# ESP8266Watch-v1-Sch.net
KiCad netlist of a schematic drawn in Altium Designer
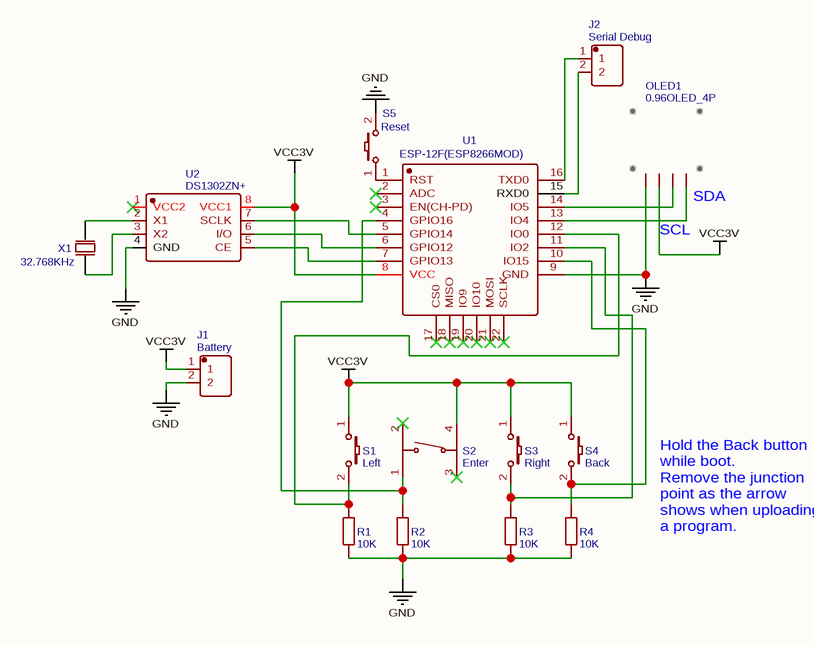
[diagram p0: ESP8266Watch-v1-Sch.schdoc]

(export (version "E")
  (design (tool "Eeschema 10.0.6"))
  (components
    (comp (ref "J1")
      (value "Battery")
      (fields (field (name "BOM_SUPPLIER PART") "C2324") (field (name "BOM_MANUFACTURER PART") "1.25T-1-2A"))
      (libsource (lib "altium-import") (part "root_0_Battery_"))
    )
    (comp (ref "J2")
      (value "Serial Debug")
      (fields (field (name "BOM_SUPPLIER PART") "C2324") (field (name "BOM_MANUFACTURER PART") "1.25T-1-2A"))
      (libsource (lib "altium-import") (part "root_0_Serial Debug_"))
    )
    (comp (ref "OLED1")
      (value "0.96OLED_4P")
      (fields (field (name "CONTRIBUTOR") "LCEDA_Lib"))
      (libsource (lib "altium-import") (part "root_0_0.96OLED_4P_"))
    )
    (comp (ref "R1")
      (value "10K")
      (fields
        (field (name "BOM_MANUFACTURER PART") "RT0603DRD0710KL")
        (field (name "BOM_SUPPLIER PART") "C136944")
        (field (name "CONTRIBUTOR") "LCSC")
      )
      (libsource (lib "altium-import") (part "root_1_10K_"))
    )
    (comp (ref "R2")
      (value "10K")
      (fields
        (field (name "BOM_MANUFACTURER PART") "RT0603DRD0710KL")
        (field (name "BOM_SUPPLIER PART") "C136944")
        (field (name "CONTRIBUTOR") "LCSC")
      )
      (libsource (lib "altium-import") (part "root_1_10K_"))
    )
    (comp (ref "R3")
      (value "10K")
      (fields
        (field (name "BOM_MANUFACTURER PART") "RT0603DRD0710KL")
        (field (name "BOM_SUPPLIER PART") "C136944")
        (field (name "CONTRIBUTOR") "LCSC")
      )
      (libsource (lib "altium-import") (part "root_1_10K_"))
    )
    (comp (ref "R4")
      (value "10K")
      (fields
        (field (name "BOM_MANUFACTURER PART") "RT0603DRD0710KL")
        (field (name "BOM_SUPPLIER PART") "C136944")
        (field (name "CONTRIBUTOR") "LCSC")
      )
      (libsource (lib "altium-import") (part "root_1_10K_"))
    )
    (comp (ref "S1")
      (value "Left")
      (fields
        (field (name "BOM_SUPPLIER PART") "C118141")
        (field (name "BOM_MANUFACTURER PART") "K2-1107ST-A4SW-06")
        (field (name "CONTRIBUTOR") "LCEDA_Lib")
      )
      (libsource (lib "altium-import") (part "root_3_Left_"))
    )
    (comp (ref "S2")
      (value "Enter")
      (fields
        (field (name "BOM_SUPPLIER PART") "C480319")
        (field (name "BOM_MANUFACTURER PART") "TS-1109S-B-F")
        (field (name "CONTRIBUTOR") "LCSC")
      )
      (libsource (lib "altium-import") (part "root_1_Enter_"))
    )
    (comp (ref "S3")
      (value "Right")
      (fields
        (field (name "BOM_SUPPLIER PART") "C118141")
        (field (name "BOM_MANUFACTURER PART") "K2-1107ST-A4SW-06")
        (field (name "CONTRIBUTOR") "LCEDA_Lib")
      )
      (libsource (lib "altium-import") (part "root_3_Right_"))
    )
    (comp (ref "S4")
      (value "Back")
      (fields
        (field (name "BOM_SUPPLIER PART") "C118141")
        (field (name "BOM_MANUFACTURER PART") "K2-1107ST-A4SW-06")
        (field (name "CONTRIBUTOR") "LCEDA_Lib")
      )
      (libsource (lib "altium-import") (part "root_3_Back_"))
    )
    (comp (ref "S5")
      (value "Reset")
      (fields
        (field (name "BOM_SUPPLIER PART") "C118141")
        (field (name "BOM_MANUFACTURER PART") "K2-1107ST-A4SW-06")
        (field (name "CONTRIBUTOR") "LCEDA_Lib")
      )
      (libsource (lib "altium-import") (part "root_1_Reset_"))
    )
    (comp (ref "U1")
      (value "ESP-12F(ESP8266MOD)")
      (fields (field (name "BOM_SUPPLIER PART") "C82891"))
      (libsource (lib "altium-import") (part "root_0_ESP-12F(ESP8266MOD)_"))
    )
    (comp (ref "U2")
      (value "DS1302ZN+")
      (fields (field (name "BOM_MANUFACTURER PART") "DS1302Z+T&R") (field (name "BOM_SUPPLIER PART") "C8959"))
      (libsource (lib "altium-import") (part "root_0_DS1302ZN+_"))
    )
    (comp (ref "X1")
      (value "32.768KHz")
      (fields
        (field (name "BOM_SUPPLIER PART") "C100098")
        (field (name "BOM_MANUFACTURER PART") "CFS-20632768DZFB")
        (field (name "CONTRIBUTOR") "LCSC")
      )
      (libsource (lib "altium-import") (part "root_1_32.768KHz_"))
    )
  )
  (nets
    (net (code "1") (name "GND") (class "Default")
      (node (ref "J1") (pin "2") (pinfunction "2_2") (pintype "passive"))
      (node (ref "OLED1") (pin "1") (pinfunction "1_1") (pintype "passive"))
      (node (ref "R1") (pin "1") (pinfunction "1_1") (pintype "passive"))
      (node (ref "R2") (pin "1") (pinfunction "1_1") (pintype "passive"))
      (node (ref "R3") (pin "1") (pinfunction "1_1") (pintype "passive"))
      (node (ref "R4") (pin "1") (pinfunction "1_1") (pintype "passive"))
      (node (ref "S5") (pin "2") (pinfunction "2_2") (pintype "passive"))
      (node (ref "U1") (pin "9") (pinfunction "GND_9") (pintype "passive"))
      (node (ref "U2") (pin "4") (pinfunction "GND_4") (pintype "passive"))
    )
    (net (code "2") (name "Net-(U1-GPIO12)") (class "Default")
      (node (ref "U1") (pin "6") (pinfunction "GPIO12_6") (pintype "passive"))
      (node (ref "U2") (pin "6") (pinfunction "I/O_6") (pintype "passive"))
    )
    (net (code "3") (name "Net-(U1-GPIO13)") (class "Default")
      (node (ref "U1") (pin "7") (pinfunction "GPIO13_7") (pintype "passive"))
      (node (ref "U2") (pin "5") (pinfunction "CE_5") (pintype "passive"))
    )
    (net (code "4") (name "Net-(U1-GPIO14)") (class "Default")
      (node (ref "U1") (pin "5") (pinfunction "GPIO14_5") (pintype "passive"))
      (node (ref "U2") (pin "7") (pinfunction "SCLK_7") (pintype "passive"))
    )
    (net (code "5") (name "Net-(U1-GPIO16)") (class "Default")
      (node (ref "R2") (pin "2") (pinfunction "2_2") (pintype "passive"))
      (node (ref "S2") (pin "1") (pinfunction "1_1") (pintype "passive"))
      (node (ref "U1") (pin "4") (pinfunction "GPIO16_4") (pintype "passive"))
    )
    (net (code "6") (name "Net-(U1-IO0)") (class "Default")
      (node (ref "R1") (pin "2") (pinfunction "2_2") (pintype "passive"))
      (node (ref "S1") (pin "2") (pinfunction "2_2") (pintype "passive"))
      (node (ref "U1") (pin "12") (pinfunction "IO0_12") (pintype "passive"))
    )
    (net (code "7") (name "Net-(U1-IO2)") (class "Default")
      (node (ref "R3") (pin "2") (pinfunction "2_2") (pintype "passive"))
      (node (ref "S3") (pin "2") (pinfunction "2_2") (pintype "passive"))
      (node (ref "U1") (pin "11") (pinfunction "IO2_11") (pintype "passive"))
    )
    (net (code "8") (name "Net-(U1-IO4)") (class "Default")
      (node (ref "OLED1") (pin "4") (pinfunction "4_4") (pintype "passive"))
      (node (ref "U1") (pin "13") (pinfunction "IO4_13") (pintype "passive"))
    )
    (net (code "9") (name "Net-(U1-IO5)") (class "Default")
      (node (ref "OLED1") (pin "3") (pinfunction "3_3") (pintype "passive"))
      (node (ref "U1") (pin "14") (pinfunction "IO5_14") (pintype "passive"))
    )
    (net (code "10") (name "Net-(U1-IO15)") (class "Default")
      (node (ref "R4") (pin "2") (pinfunction "2_2") (pintype "passive"))
      (node (ref "S4") (pin "2") (pinfunction "2_2") (pintype "passive"))
      (node (ref "U1") (pin "10") (pinfunction "IO15_10") (pintype "passive"))
    )
    (net (code "11") (name "Net-(U1-RST)") (class "Default")
      (node (ref "S5") (pin "1") (pinfunction "1_1") (pintype "passive"))
      (node (ref "U1") (pin "1") (pinfunction "RST_1") (pintype "passive"))
    )
    (net (code "12") (name "Net-(U1-RXD0)") (class "Default")
      (node (ref "J2") (pin "2") (pinfunction "2_2") (pintype "passive"))
      (node (ref "U1") (pin "15") (pinfunction "RXD0_15") (pintype "passive"))
    )
    (net (code "13") (name "Net-(U1-TXD0)") (class "Default")
      (node (ref "J2") (pin "1") (pinfunction "1_1") (pintype "passive"))
      (node (ref "U1") (pin "16") (pinfunction "TXD0_16") (pintype "passive"))
    )
    (net (code "14") (name "Net-(U2-X1)") (class "Default")
      (node (ref "U2") (pin "2") (pinfunction "X1_2") (pintype "passive"))
      (node (ref "X1") (pin "2") (pinfunction "OSC2_2") (pintype "passive"))
    )
    (net (code "15") (name "Net-(U2-X2)") (class "Default")
      (node (ref "U2") (pin "3") (pinfunction "X2_3") (pintype "passive"))
      (node (ref "X1") (pin "1") (pinfunction "OSC1_1") (pintype "passive"))
    )
    (net (code "16") (name "VCC3V") (class "Default")
      (node (ref "J1") (pin "1") (pinfunction "1_1") (pintype "passive"))
      (node (ref "OLED1") (pin "2") (pinfunction "2_2") (pintype "passive"))
      (node (ref "S1") (pin "1") (pinfunction "1_1") (pintype "passive"))
      (node (ref "S2") (pin "4") (pinfunction "4_4") (pintype "passive"))
      (node (ref "S3") (pin "1") (pinfunction "1_1") (pintype "passive"))
      (node (ref "S4") (pin "1") (pinfunction "1_1") (pintype "passive"))
      (node (ref "U1") (pin "8") (pinfunction "VCC_8") (pintype "passive"))
      (node (ref "U2") (pin "8") (pinfunction "VCC1_8") (pintype "passive"))
    )
    (net (code "17") (name "unconnected-(S2-Pad2)") (class "Default")
      (node (ref "S2") (pin "2") (pinfunction "2_2") (pintype "passive+no_connect"))
    )
    (net (code "18") (name "unconnected-(S2-Pad3)") (class "Default")
      (node (ref "S2") (pin "3") (pinfunction "3_3") (pintype "passive+no_connect"))
    )
    (net (code "19") (name "unconnected-(U1-ADC-Pad2)") (class "Default")
      (node (ref "U1") (pin "2") (pinfunction "ADC_2") (pintype "passive+no_connect"))
    )
    (net (code "20") (name "unconnected-(U1-CS0-Pad17)") (class "Default")
      (node (ref "U1") (pin "17") (pinfunction "CS0_17") (pintype "passive+no_connect"))
    )
    (net (code "21") (name "unconnected-(U1-EN(CH-PD)-Pad3)") (class "Default")
      (node (ref "U1") (pin "3") (pinfunction "EN(CH-PD)_3") (pintype "passive+no_connect"))
    )
    (net (code "22") (name "unconnected-(U1-IO9-Pad19)") (class "Default")
      (node (ref "U1") (pin "19") (pinfunction "IO9_19") (pintype "passive+no_connect"))
    )
    (net (code "23") (name "unconnected-(U1-IO10-Pad20)") (class "Default")
      (node (ref "U1") (pin "20") (pinfunction "IO10_20") (pintype "passive+no_connect"))
    )
    (net (code "24") (name "unconnected-(U1-MISO-Pad18)") (class "Default")
      (node (ref "U1") (pin "18") (pinfunction "MISO_18") (pintype "passive+no_connect"))
    )
    (net (code "25") (name "unconnected-(U1-MOSI-Pad21)") (class "Default")
      (node (ref "U1") (pin "21") (pinfunction "MOSI_21") (pintype "passive+no_connect"))
    )
    (net (code "26") (name "unconnected-(U1-SCLK-Pad22)") (class "Default")
      (node (ref "U1") (pin "22") (pinfunction "SCLK_22") (pintype "passive+no_connect"))
    )
    (net (code "27") (name "unconnected-(U2-VCC2-Pad1)") (class "Default")
      (node (ref "U2") (pin "1") (pinfunction "VCC2_1") (pintype "passive+no_connect"))
    )
  )
)
